# ALSN_v1.net
KiCad netlist of a schematic drawn in EAGLE
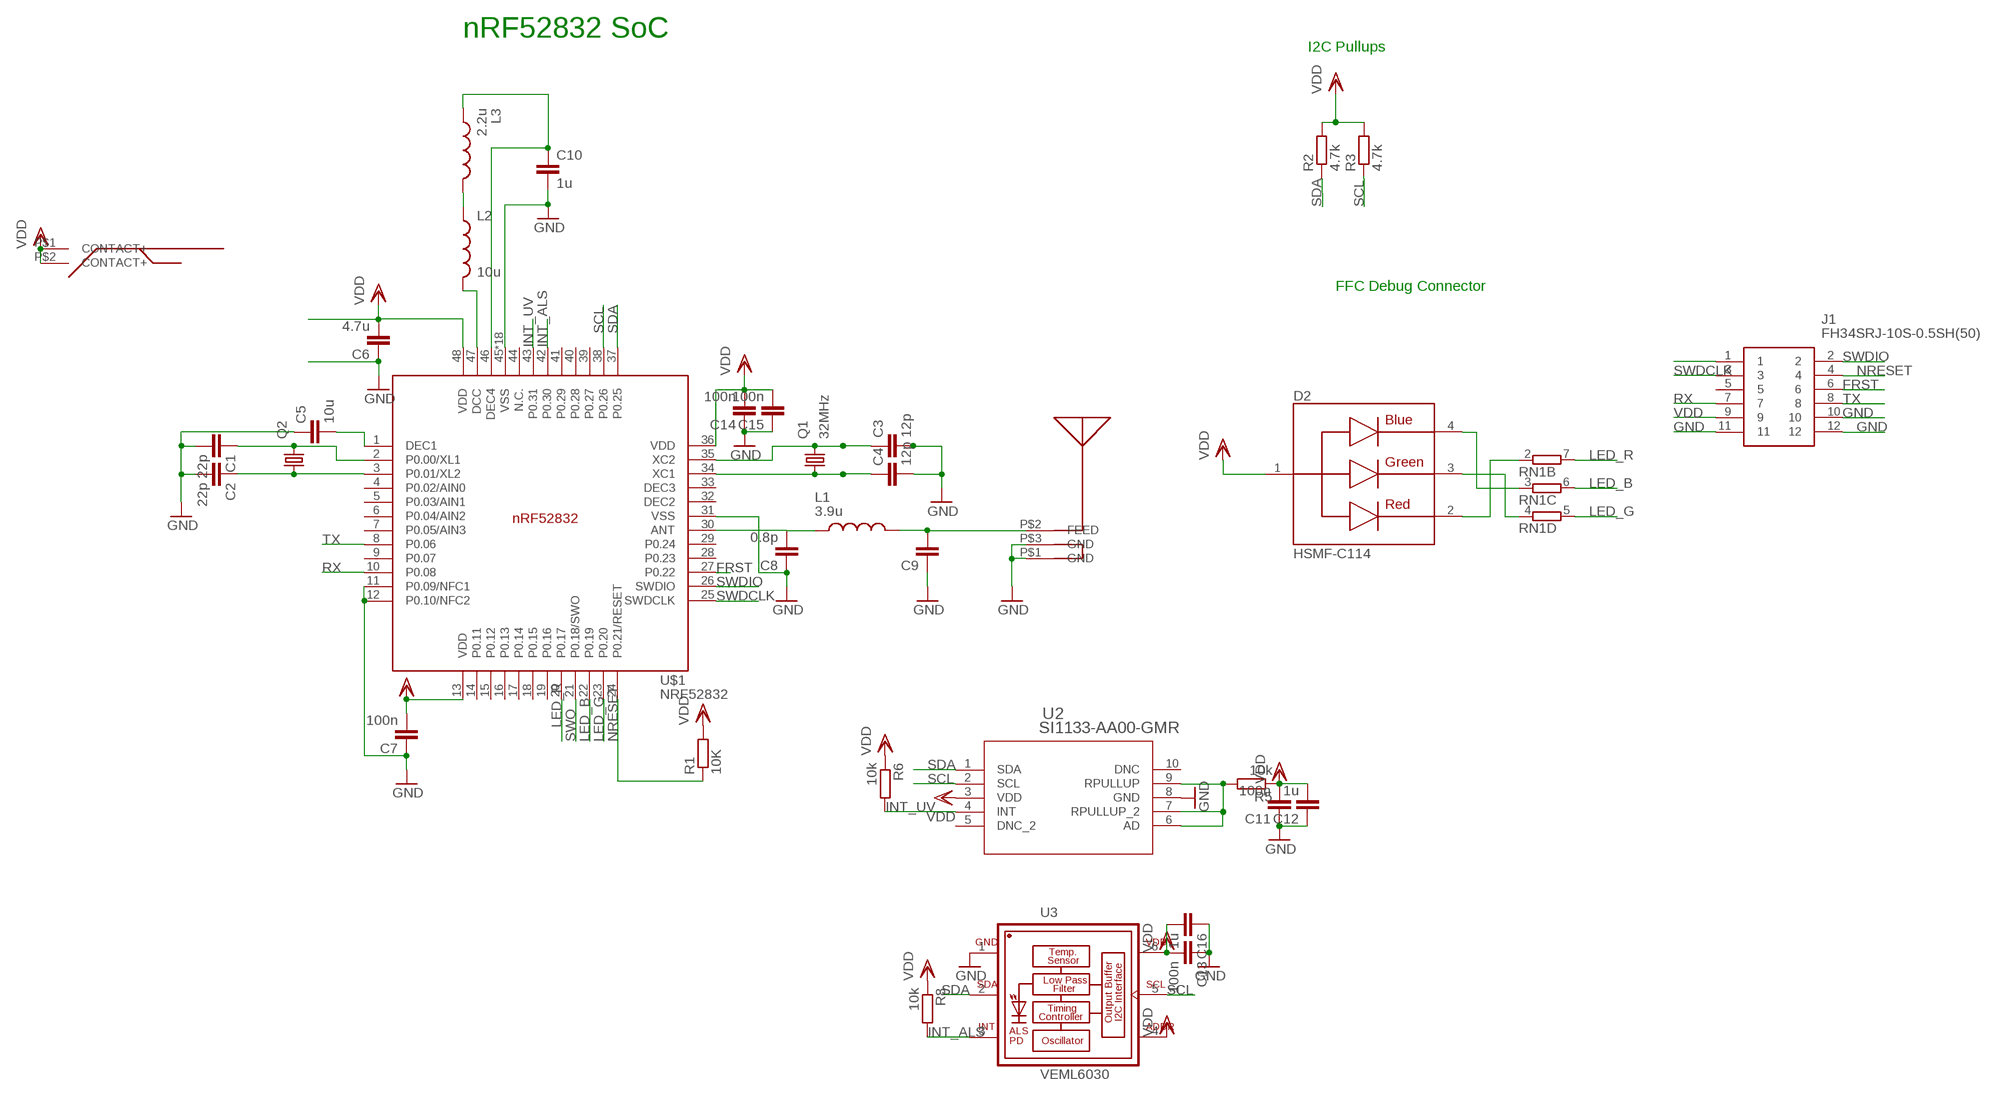
[diagram p0: schematic, sheet 1]

(export (version "E")
  (design (tool "Eeschema 10.0.6"))
  (components
    (comp (ref "C1")
      (value "22p")
      (footprint "eagle-import:C0402")
      (libsource (lib "eagle-import") (part "CC0402"))
    )
    (comp (ref "C2")
      (value "22p")
      (footprint "eagle-import:C0402")
      (libsource (lib "eagle-import") (part "CC0402"))
    )
    (comp (ref "C3")
      (value "12p")
      (footprint "eagle-import:C0402")
      (libsource (lib "eagle-import") (part "CC0402"))
    )
    (comp (ref "C4")
      (value "12p")
      (footprint "eagle-import:C0402")
      (libsource (lib "eagle-import") (part "CC0402"))
    )
    (comp (ref "C5")
      (value "10u")
      (footprint "eagle-import:C0402")
      (libsource (lib "eagle-import") (part "CC0402"))
    )
    (comp (ref "C6")
      (value "4.7u")
      (footprint "eagle-import:C0402")
      (libsource (lib "eagle-import") (part "CC0402"))
    )
    (comp (ref "C7")
      (value "100n")
      (footprint "eagle-import:C0603R")
      (libsource (lib "eagle-import") (part "CC0603R"))
    )
    (comp (ref "C8")
      (value "0.8p")
      (footprint "eagle-import:C0402")
      (libsource (lib "eagle-import") (part "CC0402"))
    )
    (comp (ref "C9")
      (value "1.2p")
      (footprint "eagle-import:C0402")
      (libsource (lib "eagle-import") (part "CC0402"))
    )
    (comp (ref "C10")
      (value "1u")
      (footprint "eagle-import:C0402")
      (libsource (lib "eagle-import") (part "CC0402"))
    )
    (comp (ref "C11")
      (value "100n")
      (footprint "eagle-import:C0402")
      (libsource (lib "eagle-import") (part "CC0402"))
    )
    (comp (ref "C12")
      (value "1u")
      (footprint "eagle-import:C0402")
      (libsource (lib "eagle-import") (part "CC0402"))
    )
    (comp (ref "C13")
      (value "100n")
      (footprint "eagle-import:C0402")
      (libsource (lib "eagle-import") (part "CC0402"))
    )
    (comp (ref "C14")
      (value "100n")
      (footprint "eagle-import:C0402")
      (libsource (lib "eagle-import") (part "CC0402"))
    )
    (comp (ref "C15")
      (value "100n")
      (footprint "eagle-import:C0402")
      (libsource (lib "eagle-import") (part "CC0402"))
    )
    (comp (ref "C16")
      (value "1u")
      (footprint "eagle-import:C0402")
      (libsource (lib "eagle-import") (part "CC0402"))
    )
    (comp (ref "D2")
      (value "HSMF-C114")
      (footprint "eagle-import:DIOSC160X150X35-4N")
      (fields (field (name "MF") "Broadcom Limited"))
      (libsource (lib "eagle-import") (part "HSMF-C114"))
    )
    (comp (ref "J1")
      (value "FH34SRJ-10S-0.5SH(50)")
      (footprint "eagle-import:FH34SRJ10S05SH50")
      (fields (field (name "MF") "Hirose Connector"))
      (libsource (lib "eagle-import") (part "FH34SRJ-10S-0.5SH(50)"))
    )
    (comp (ref "L1")
      (value "3.9u")
      (footprint "eagle-import:INDC0402X26N")
      (fields (field (name "MF") "TDK") (field (name "MP") "MHQ0402P7N5JT000"))
      (libsource (lib "eagle-import") (part "MHQ0402P7N5JT000"))
    )
    (comp (ref "L2")
      (value "10u")
      (footprint "eagle-import:L0603")
      (libsource (lib "eagle-import") (part "INDUCTOR"))
    )
    (comp (ref "L3")
      (value "2.2u")
      (footprint "eagle-import:INDC0402X26N")
      (fields (field (name "MF") "TDK") (field (name "MP") "MHQ0402P7N5JT000"))
      (libsource (lib "eagle-import") (part "MHQ0402P7N5JT000"))
    )
    (comp (ref "Q1")
      (value "32MHz")
      (footprint "eagle-import:2.0X1.6_KX-5")
      (libsource (lib "eagle-import") (part "KX-5"))
    )
    (comp (ref "Q2")
      (value "KX-327-RT")
      (footprint "eagle-import:2.0X1.2")
      (libsource (lib "eagle-import") (part "KX-327-RT"))
    )
    (comp (ref "R1")
      (value "10K")
      (footprint "eagle-import:R0402")
      (libsource (lib "eagle-import") (part "RR0402"))
    )
    (comp (ref "R2")
      (value "4.7k")
      (footprint "eagle-import:R0402")
      (libsource (lib "eagle-import") (part "RR0402"))
    )
    (comp (ref "R3")
      (value "4.7k")
      (footprint "eagle-import:R0402")
      (libsource (lib "eagle-import") (part "RR0402"))
    )
    (comp (ref "R5")
      (value "10k")
      (footprint "eagle-import:R0402")
      (libsource (lib "eagle-import") (part "RR0402"))
    )
    (comp (ref "R6")
      (value "10k")
      (footprint "eagle-import:R0402")
      (libsource (lib "eagle-import") (part "RR0402"))
    )
    (comp (ref "R8")
      (value "10k")
      (footprint "eagle-import:R0402")
      (libsource (lib "eagle-import") (part "RR0402"))
    )
    (comp (ref "RN1")
      (value "4R-N0402ARV341")
      (footprint "eagle-import:4X0402ARV341")
      (libsource (lib "eagle-import") (part "4R-N0402ARV341"))
    )
    (comp (ref "U$1")
      (value "NRF52832")
      (footprint "eagle-import:QFN40P600X600X90-48_N")
      (libsource (lib "eagle-import") (part "NRF52832"))
    )
    (comp (ref "U$2")
      (value "CR2032-THT")
      (footprint "eagle-import:CR2032-THT")
      (libsource (lib "eagle-import") (part "CR2032-THT"))
    )
    (comp (ref "U$4")
      (value "CHIPANTENNAL2")
      (footprint "eagle-import:CHIPANTENNAL2")
      (libsource (lib "eagle-import") (part "CHIPANTENNAL2"))
    )
    (comp (ref "U2")
      (value "SI1133-AA00-GMR")
      (footprint "eagle-import:10QFN_2X2_SIL")
      (fields (field (name "COPYRIGHT") "Copyright (C) 2018 Accelerated Designs. All rights reserved"))
      (libsource (lib "eagle-import") (part "SI1133-AA00-GMR"))
    )
    (comp (ref "U3")
      (value "VEML6030")
      (footprint "eagle-import:VISHAY_VEML6030_2X2X0.87")
      (fields (field (name "MF") "Vishay"))
      (libsource (lib "eagle-import") (part "VEML6030"))
    )
  )
  (nets
    (net (code "1") (name "/FRST") (class "Default")
      (node (ref "J1") (pin "6") (pinfunction "6_6") (pintype "bidirectional"))
      (node (ref "U$1") (pin "27") (pinfunction "P0.22_27") (pintype "bidirectional"))
    )
    (net (code "2") (name "/INT_ALS") (class "Default")
      (node (ref "R8") (pin "2") (pinfunction "2_2") (pintype "passive"))
      (node (ref "U$1") (pin "42") (pinfunction "P0.30_42") (pintype "bidirectional"))
      (node (ref "U3") (pin "3") (pinfunction "INT_3") (pintype "output"))
    )
    (net (code "3") (name "/INT_UV") (class "Default")
      (node (ref "R6") (pin "2") (pinfunction "2_2") (pintype "passive"))
      (node (ref "U$1") (pin "43") (pinfunction "P0.31_43") (pintype "bidirectional"))
      (node (ref "U2") (pin "4") (pinfunction "INT_4") (pintype "bidirectional"))
    )
    (net (code "4") (name "/LED_B") (class "Default")
      (node (ref "RN1") (pin "6") (pinfunction "2_6") (pintype "passive"))
      (node (ref "U$1") (pin "22") (pinfunction "P0.19_22") (pintype "bidirectional"))
    )
    (net (code "5") (name "/LED_G") (class "Default")
      (node (ref "RN1") (pin "5") (pinfunction "2_5") (pintype "passive"))
      (node (ref "U$1") (pin "23") (pinfunction "P0.20_23") (pintype "bidirectional"))
    )
    (net (code "6") (name "/LED_R") (class "Default")
      (node (ref "RN1") (pin "7") (pinfunction "2_7") (pintype "passive"))
      (node (ref "U$1") (pin "20") (pinfunction "P0.17_20") (pintype "bidirectional"))
    )
    (net (code "7") (name "/NRESET") (class "Default")
      (node (ref "J1") (pin "4") (pinfunction "4_4") (pintype "bidirectional"))
      (node (ref "R1") (pin "1") (pinfunction "1_1") (pintype "passive"))
      (node (ref "U$1") (pin "24") (pinfunction "P0.21/RESET_24") (pintype "bidirectional"))
    )
    (net (code "8") (name "/RX") (class "Default")
      (node (ref "J1") (pin "7") (pinfunction "7_7") (pintype "bidirectional"))
      (node (ref "U$1") (pin "10") (pinfunction "P0.08_10") (pintype "bidirectional"))
    )
    (net (code "9") (name "/SCL") (class "Default")
      (node (ref "R3") (pin "1") (pinfunction "1_1") (pintype "passive"))
      (node (ref "U$1") (pin "38") (pinfunction "P0.26_38") (pintype "bidirectional"))
      (node (ref "U2") (pin "2") (pinfunction "SCL_2") (pintype "input"))
      (node (ref "U3") (pin "5") (pinfunction "SCL_5") (pintype "input"))
    )
    (net (code "10") (name "/SDA") (class "Default")
      (node (ref "R2") (pin "1") (pinfunction "1_1") (pintype "passive"))
      (node (ref "U$1") (pin "37") (pinfunction "P0.25_37") (pintype "bidirectional"))
      (node (ref "U2") (pin "1") (pinfunction "SDA_1") (pintype "bidirectional"))
      (node (ref "U3") (pin "2") (pinfunction "SDA_2") (pintype "bidirectional"))
    )
    (net (code "11") (name "/SWDCLK") (class "Default")
      (node (ref "J1") (pin "3") (pinfunction "3_3") (pintype "bidirectional"))
      (node (ref "U$1") (pin "25") (pinfunction "SWDCLK_25") (pintype "input"))
    )
    (net (code "12") (name "/SWDIO") (class "Default")
      (node (ref "J1") (pin "2") (pinfunction "2_2") (pintype "bidirectional"))
      (node (ref "U$1") (pin "26") (pinfunction "SWDIO_26") (pintype "bidirectional"))
    )
    (net (code "13") (name "/SWO") (class "Default")
      (node (ref "U$1") (pin "21") (pinfunction "P0.18/SWO_21") (pintype "bidirectional"))
    )
    (net (code "14") (name "/TX") (class "Default")
      (node (ref "J1") (pin "8") (pinfunction "8_8") (pintype "bidirectional"))
      (node (ref "U$1") (pin "8") (pinfunction "P0.06_8") (pintype "bidirectional"))
    )
    (net (code "15") (name "GND") (class "Default")
      (node (ref "C1") (pin "2") (pinfunction "2_2") (pintype "passive"))
      (node (ref "C10") (pin "2") (pinfunction "2_2") (pintype "passive"))
      (node (ref "C11") (pin "1") (pinfunction "1_1") (pintype "passive"))
      (node (ref "C12") (pin "1") (pinfunction "1_1") (pintype "passive"))
      (node (ref "C13") (pin "1") (pinfunction "1_1") (pintype "passive"))
      (node (ref "C14") (pin "1") (pinfunction "1_1") (pintype "passive"))
      (node (ref "C15") (pin "1") (pinfunction "1_1") (pintype "passive"))
      (node (ref "C16") (pin "1") (pinfunction "1_1") (pintype "passive"))
      (node (ref "C2") (pin "2") (pinfunction "2_2") (pintype "passive"))
      (node (ref "C3") (pin "2") (pinfunction "2_2") (pintype "passive"))
      (node (ref "C4") (pin "2") (pinfunction "2_2") (pintype "passive"))
      (node (ref "C5") (pin "1") (pinfunction "1_1") (pintype "passive"))
      (node (ref "C6") (pin "1") (pinfunction "1_1") (pintype "passive"))
      (node (ref "C7") (pin "1") (pinfunction "1_1") (pintype "passive"))
      (node (ref "C8") (pin "1") (pinfunction "1_1") (pintype "passive"))
      (node (ref "C9") (pin "1") (pinfunction "1_1") (pintype "passive"))
      (node (ref "J1") (pin "10") (pinfunction "10_10") (pintype "bidirectional"))
      (node (ref "J1") (pin "11") (pinfunction "11_11") (pintype "bidirectional"))
      (node (ref "J1") (pin "12") (pinfunction "12_12") (pintype "bidirectional"))
      (node (ref "U$1") (pin "11") (pinfunction "P0.09/NFC1_11") (pintype "bidirectional"))
      (node (ref "U$1") (pin "12") (pinfunction "P0.10/NFC2_12") (pintype "bidirectional"))
      (node (ref "U$1") (pin "31") (pinfunction "VSS_31") (pintype "bidirectional"))
      (node (ref "U$1") (pin "45") (pinfunction "VSS_45") (pintype "power_in"))
      (node (ref "U$1") (pin "PAD") (pinfunction "VSS_PAD") (pintype "power_in"))
      (node (ref "U$1") (pin "PAD@VIA01") (pinfunction "VSS_PAD@VIA01") (pintype "power_in"))
      (node (ref "U$1") (pin "PAD@VIA02") (pinfunction "VSS_PAD@VIA02") (pintype "power_in"))
      (node (ref "U$1") (pin "PAD@VIA03") (pinfunction "VSS_PAD@VIA03") (pintype "power_in"))
      (node (ref "U$1") (pin "PAD@VIA04") (pinfunction "VSS_PAD@VIA04") (pintype "power_in"))
      (node (ref "U$1") (pin "PAD@VIA05") (pinfunction "VSS_PAD@VIA05") (pintype "power_in"))
      (node (ref "U$1") (pin "PAD@VIA06") (pinfunction "VSS_PAD@VIA06") (pintype "power_in"))
      (node (ref "U$1") (pin "PAD@VIA07") (pinfunction "VSS_PAD@VIA07") (pintype "power_in"))
      (node (ref "U$1") (pin "PAD@VIA08") (pinfunction "VSS_PAD@VIA08") (pintype "power_in"))
      (node (ref "U$1") (pin "PAD@VIA09") (pinfunction "VSS_PAD@VIA09") (pintype "power_in"))
      (node (ref "U$1") (pin "PAD@VIA10") (pinfunction "VSS_PAD@VIA10") (pintype "power_in"))
      (node (ref "U$1") (pin "PAD@VIA11") (pinfunction "VSS_PAD@VIA11") (pintype "power_in"))
      (node (ref "U$1") (pin "PAD@VIA12") (pinfunction "VSS_PAD@VIA12") (pintype "power_in"))
      (node (ref "U$1") (pin "PAD@VIA13") (pinfunction "VSS_PAD@VIA13") (pintype "power_in"))
      (node (ref "U$1") (pin "PAD@VIA14") (pinfunction "VSS_PAD@VIA14") (pintype "power_in"))
      (node (ref "U$1") (pin "PAD@VIA15") (pinfunction "VSS_PAD@VIA15") (pintype "power_in"))
      (node (ref "U$1") (pin "PAD@VIA16") (pinfunction "VSS_PAD@VIA16") (pintype "power_in"))
      (node (ref "U$4") (pin "P$1") (pinfunction "GND_P$1") (pintype "bidirectional"))
      (node (ref "U$4") (pin "P$3") (pinfunction "GND_P$3") (pintype "bidirectional"))
      (node (ref "U2") (pin "8") (pinfunction "GND_8") (pintype "passive"))
      (node (ref "U3") (pin "1") (pinfunction "GND_1") (pintype "power_in"))
    )
    (net (code "16") (name "Net-(L2-Pad1)") (class "Default")
      (node (ref "L2") (pin "1") (pinfunction "1_1") (pintype "passive"))
      (node (ref "L3") (pin "2") (pinfunction "2_2") (pintype "passive"))
    )
    (net (code "17") (name "Net-(Q1-2)") (class "Default")
      (node (ref "C3") (pin "1") (pinfunction "1_1") (pintype "passive"))
      (node (ref "Q1") (pin "3") (pinfunction "2_3") (pintype "passive"))
      (node (ref "U$1") (pin "35") (pinfunction "XC2_35") (pintype "output"))
    )
    (net (code "18") (name "Net-(RN1B-1)") (class "Default")
      (node (ref "D2") (pin "2") (pinfunction "2_2") (pintype "passive"))
      (node (ref "RN1") (pin "2") (pinfunction "1_2") (pintype "passive"))
    )
    (net (code "19") (name "Net-(RN1C-1)") (class "Default")
      (node (ref "D2") (pin "4") (pinfunction "4_4") (pintype "passive"))
      (node (ref "RN1") (pin "3") (pinfunction "1_3") (pintype "passive"))
    )
    (net (code "20") (name "Net-(RN1D-1)") (class "Default")
      (node (ref "D2") (pin "3") (pinfunction "3_3") (pintype "passive"))
      (node (ref "RN1") (pin "4") (pinfunction "1_4") (pintype "passive"))
    )
    (net (code "21") (name "Net-(U$1-ANT)") (class "Default")
      (node (ref "C8") (pin "2") (pinfunction "2_2") (pintype "passive"))
      (node (ref "L1") (pin "1") (pinfunction "1_1") (pintype "passive"))
      (node (ref "U$1") (pin "30") (pinfunction "ANT_30") (pintype "bidirectional"))
    )
    (net (code "22") (name "Net-(U$1-DCC)") (class "Default")
      (node (ref "L2") (pin "2") (pinfunction "2_2") (pintype "passive"))
      (node (ref "U$1") (pin "47") (pinfunction "DCC_47") (pintype "output"))
    )
    (net (code "23") (name "Net-(U$1-DEC1)") (class "Default")
      (node (ref "C5") (pin "2") (pinfunction "2_2") (pintype "passive"))
      (node (ref "U$1") (pin "1") (pinfunction "DEC1_1") (pintype "power_in"))
    )
    (net (code "24") (name "Net-(U$1-DEC4)") (class "Default")
      (node (ref "C10") (pin "1") (pinfunction "1_1") (pintype "passive"))
      (node (ref "L3") (pin "1") (pinfunction "1_1") (pintype "passive"))
      (node (ref "U$1") (pin "46") (pinfunction "DEC4_46") (pintype "power_in"))
    )
    (net (code "25") (name "Net-(U$1-P0.00{slash}XL1)") (class "Default")
      (node (ref "C1") (pin "1") (pinfunction "1_1") (pintype "passive"))
      (node (ref "Q2") (pin "2") (pinfunction "2_2") (pintype "passive"))
      (node (ref "U$1") (pin "2") (pinfunction "P0.00/XL1_2") (pintype "bidirectional"))
    )
    (net (code "26") (name "Net-(U$1-P0.01{slash}XL2)") (class "Default")
      (node (ref "C2") (pin "1") (pinfunction "1_1") (pintype "passive"))
      (node (ref "Q2") (pin "1") (pinfunction "1_1") (pintype "passive"))
      (node (ref "U$1") (pin "3") (pinfunction "P0.01/XL2_3") (pintype "bidirectional"))
    )
    (net (code "27") (name "Net-(U$1-XC1)") (class "Default")
      (node (ref "C4") (pin "1") (pinfunction "1_1") (pintype "passive"))
      (node (ref "Q1") (pin "1") (pinfunction "1_1") (pintype "passive"))
      (node (ref "U$1") (pin "34") (pinfunction "XC1_34") (pintype "input"))
    )
    (net (code "28") (name "Net-(U$4-FEED)") (class "Default")
      (node (ref "C9") (pin "2") (pinfunction "2_2") (pintype "passive"))
      (node (ref "L1") (pin "2") (pinfunction "2_2") (pintype "passive"))
      (node (ref "U$4") (pin "P$2") (pinfunction "FEED_P$2") (pintype "bidirectional"))
    )
    (net (code "29") (name "Net-(U2-AD)") (class "Default")
      (node (ref "R5") (pin "2") (pinfunction "2_2") (pintype "passive"))
      (node (ref "U2") (pin "6") (pinfunction "AD_6") (pintype "input"))
      (node (ref "U2") (pin "7") (pinfunction "RPULLUP_2_7") (pintype "input"))
      (node (ref "U2") (pin "9") (pinfunction "RPULLUP_9") (pintype "input"))
    )
    (net (code "30") (name "VDD") (class "Default")
      (node (ref "C11") (pin "2") (pinfunction "2_2") (pintype "passive"))
      (node (ref "C12") (pin "2") (pinfunction "2_2") (pintype "passive"))
      (node (ref "C13") (pin "2") (pinfunction "2_2") (pintype "passive"))
      (node (ref "C14") (pin "2") (pinfunction "2_2") (pintype "passive"))
      (node (ref "C15") (pin "2") (pinfunction "2_2") (pintype "passive"))
      (node (ref "C16") (pin "2") (pinfunction "2_2") (pintype "passive"))
      (node (ref "C6") (pin "2") (pinfunction "2_2") (pintype "passive"))
      (node (ref "C7") (pin "2") (pinfunction "2_2") (pintype "passive"))
      (node (ref "D2") (pin "1") (pinfunction "1_1") (pintype "passive"))
      (node (ref "J1") (pin "9") (pinfunction "9_9") (pintype "bidirectional"))
      (node (ref "R1") (pin "2") (pinfunction "2_2") (pintype "passive"))
      (node (ref "R2") (pin "2") (pinfunction "2_2") (pintype "passive"))
      (node (ref "R3") (pin "2") (pinfunction "2_2") (pintype "passive"))
      (node (ref "R5") (pin "1") (pinfunction "1_1") (pintype "passive"))
      (node (ref "R6") (pin "1") (pinfunction "1_1") (pintype "passive"))
      (node (ref "R8") (pin "1") (pinfunction "1_1") (pintype "passive"))
      (node (ref "U$1") (pin "13") (pinfunction "VDD_13") (pintype "power_in"))
      (node (ref "U$1") (pin "36") (pinfunction "VDD_36") (pintype "power_in"))
      (node (ref "U$1") (pin "48") (pinfunction "VDD_48") (pintype "power_in"))
      (node (ref "U$2") (pin "P$1") (pinfunction "CONTACT+_P$1") (pintype "bidirectional"))
      (node (ref "U$2") (pin "P$2") (pinfunction "CONTACT+_P$2") (pintype "bidirectional"))
      (node (ref "U2") (pin "3") (pinfunction "VDD_3") (pintype "power_in"))
      (node (ref "U3") (pin "4") (pinfunction "ADDR_4") (pintype "bidirectional"))
      (node (ref "U3") (pin "6") (pinfunction "VDD_6") (pintype "power_in"))
    )
    (net (code "31") (name "unconnected-(J1-Pad1)") (class "Default")
      (node (ref "J1") (pin "1") (pinfunction "1_1") (pintype "bidirectional"))
    )
    (net (code "32") (name "unconnected-(J1-Pad5)") (class "Default")
      (node (ref "J1") (pin "5") (pinfunction "5_5") (pintype "bidirectional"))
    )
    (net (code "33") (name "unconnected-(U$1-DEC2-Pad32)") (class "Default")
      (node (ref "U$1") (pin "32") (pinfunction "DEC2_32") (pintype "bidirectional"))
    )
    (net (code "34") (name "unconnected-(U$1-DEC3-Pad33)") (class "Default")
      (node (ref "U$1") (pin "33") (pinfunction "DEC3_33") (pintype "bidirectional"))
    )
    (net (code "35") (name "unconnected-(U$1-N.C.-Pad44)") (class "Default")
      (node (ref "U$1") (pin "44") (pinfunction "N.C._44") (pintype "no_connect"))
    )
    (net (code "36") (name "unconnected-(U$1-P0.02{slash}AIN0-Pad4)") (class "Default")
      (node (ref "U$1") (pin "4") (pinfunction "P0.02/AIN0_4") (pintype "bidirectional"))
    )
    (net (code "37") (name "unconnected-(U$1-P0.03{slash}AIN1-Pad5)") (class "Default")
      (node (ref "U$1") (pin "5") (pinfunction "P0.03/AIN1_5") (pintype "bidirectional"))
    )
    (net (code "38") (name "unconnected-(U$1-P0.04{slash}AIN2-Pad6)") (class "Default")
      (node (ref "U$1") (pin "6") (pinfunction "P0.04/AIN2_6") (pintype "bidirectional"))
    )
    (net (code "39") (name "unconnected-(U$1-P0.05{slash}AIN3-Pad7)") (class "Default")
      (node (ref "U$1") (pin "7") (pinfunction "P0.05/AIN3_7") (pintype "bidirectional"))
    )
    (net (code "40") (name "unconnected-(U$1-P0.07-Pad9)") (class "Default")
      (node (ref "U$1") (pin "9") (pinfunction "P0.07_9") (pintype "bidirectional"))
    )
    (net (code "41") (name "unconnected-(U$1-P0.11-Pad14)") (class "Default")
      (node (ref "U$1") (pin "14") (pinfunction "P0.11_14") (pintype "bidirectional"))
    )
    (net (code "42") (name "unconnected-(U$1-P0.12-Pad15)") (class "Default")
      (node (ref "U$1") (pin "15") (pinfunction "P0.12_15") (pintype "bidirectional"))
    )
    (net (code "43") (name "unconnected-(U$1-P0.13-Pad16)") (class "Default")
      (node (ref "U$1") (pin "16") (pinfunction "P0.13_16") (pintype "bidirectional"))
    )
    (net (code "44") (name "unconnected-(U$1-P0.14-Pad17)") (class "Default")
      (node (ref "U$1") (pin "17") (pinfunction "P0.14_17") (pintype "bidirectional"))
    )
    (net (code "45") (name "unconnected-(U$1-P0.15-Pad18)") (class "Default")
      (node (ref "U$1") (pin "18") (pinfunction "P0.15_18") (pintype "bidirectional"))
    )
    (net (code "46") (name "unconnected-(U$1-P0.16-Pad19)") (class "Default")
      (node (ref "U$1") (pin "19") (pinfunction "P0.16_19") (pintype "bidirectional"))
    )
    (net (code "47") (name "unconnected-(U$1-P0.23-Pad28)") (class "Default")
      (node (ref "U$1") (pin "28") (pinfunction "P0.23_28") (pintype "bidirectional"))
    )
    (net (code "48") (name "unconnected-(U$1-P0.24-Pad29)") (class "Default")
      (node (ref "U$1") (pin "29") (pinfunction "P0.24_29") (pintype "bidirectional"))
    )
    (net (code "49") (name "unconnected-(U$1-P0.27-Pad39)") (class "Default")
      (node (ref "U$1") (pin "39") (pinfunction "P0.27_39") (pintype "bidirectional"))
    )
    (net (code "50") (name "unconnected-(U$1-P0.28-Pad40)") (class "Default")
      (node (ref "U$1") (pin "40") (pinfunction "P0.28_40") (pintype "bidirectional"))
    )
    (net (code "51") (name "unconnected-(U$1-P0.29-Pad41)") (class "Default")
      (node (ref "U$1") (pin "41") (pinfunction "P0.29_41") (pintype "bidirectional"))
    )
    (net (code "52") (name "unconnected-(U2-DNC-Pad10)") (class "Default")
      (node (ref "U2") (pin "10") (pinfunction "DNC_10") (pintype "no_connect"))
    )
    (net (code "53") (name "unconnected-(U2-DNC_2-Pad5)") (class "Default")
      (node (ref "U2") (pin "5") (pinfunction "DNC_2_5") (pintype "no_connect"))
    )
  )
)
